# bb-meter-mk-1_0.net
KiCad netlist of a schematic drawn in EAGLE
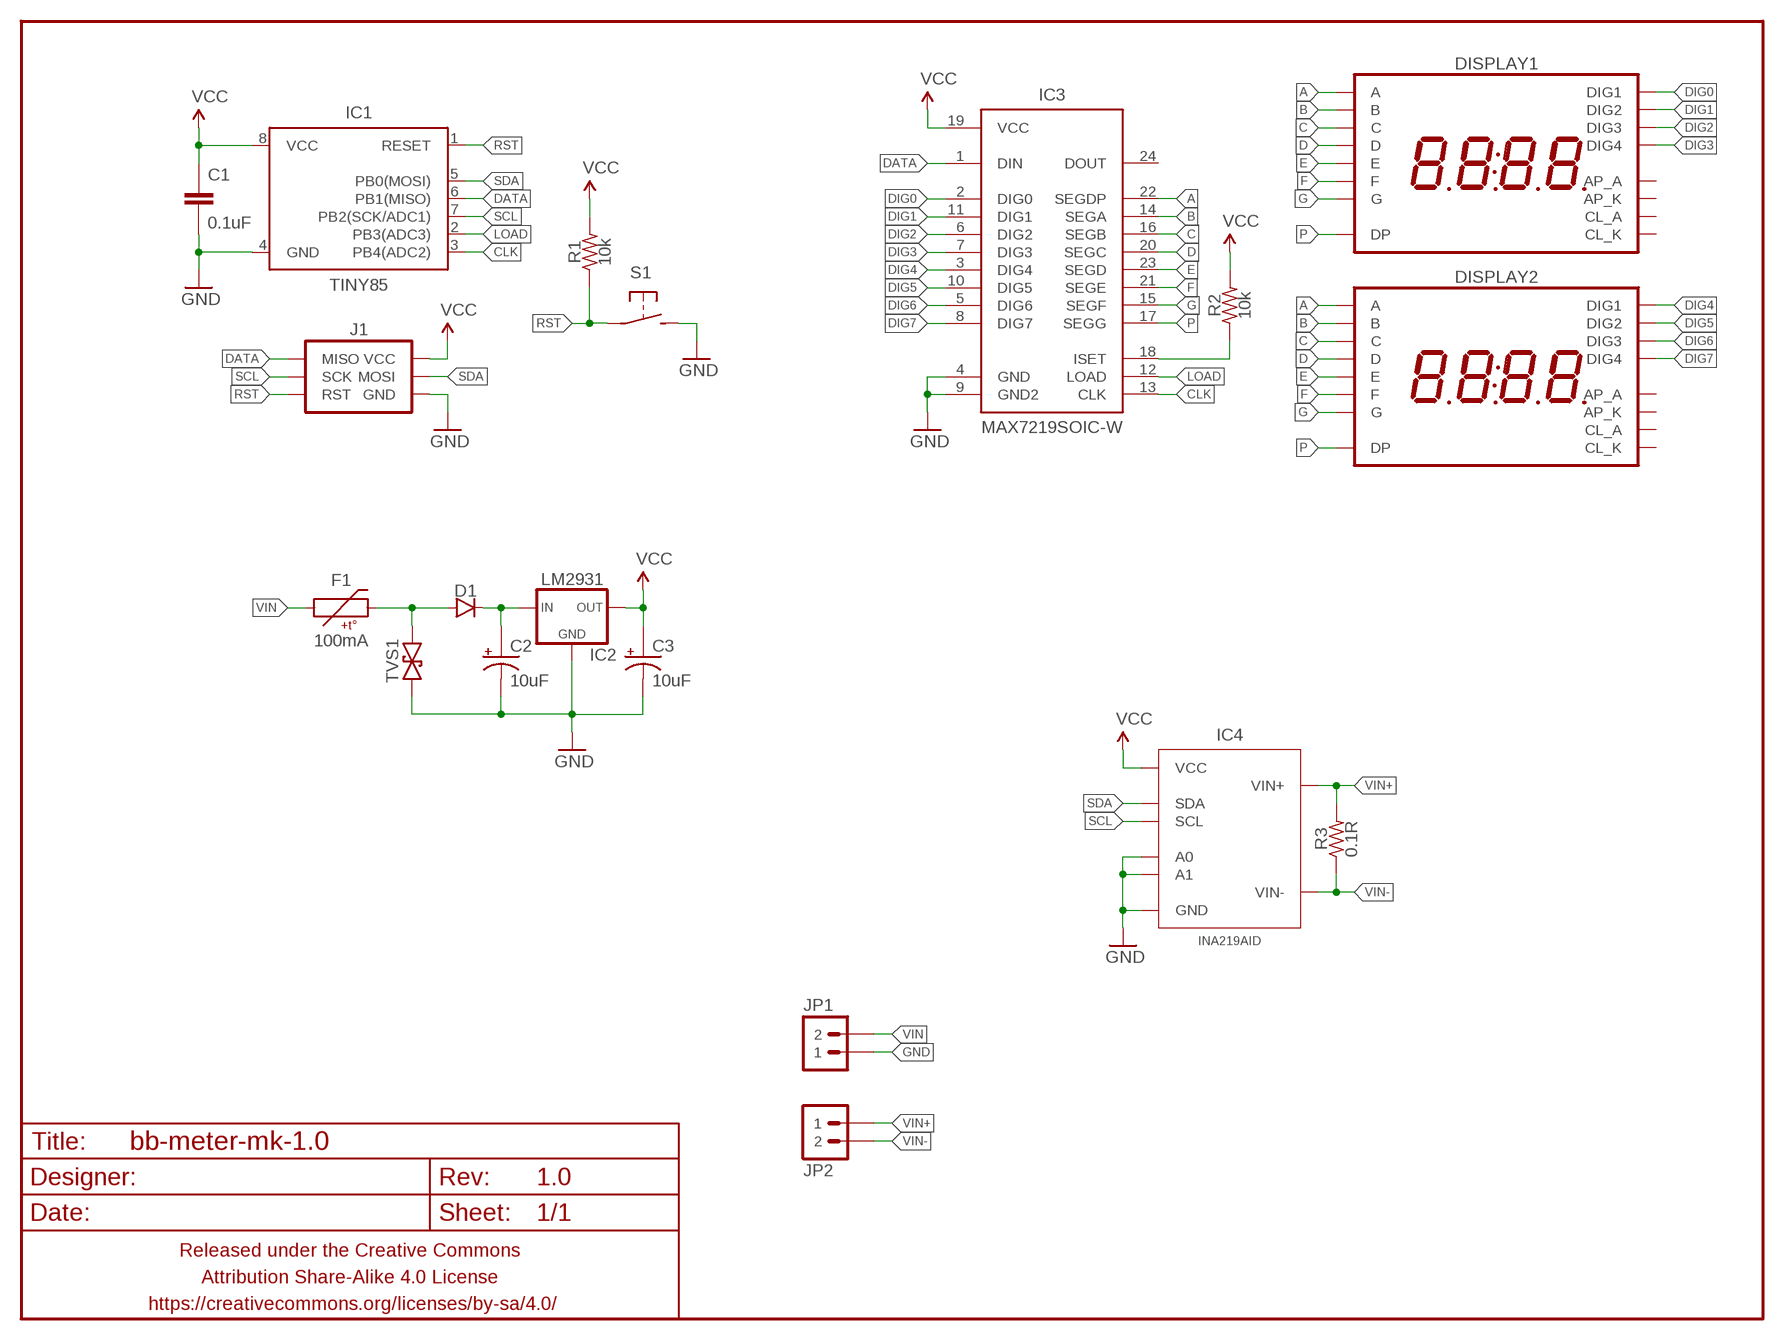
[diagram p0: schematic, sheet 1]

(export (version "E")
  (design (tool "Eeschema 10.0.6"))
  (components
    (comp (ref "C1")
      (value "0.1uF")
      (footprint "eagle-import:C025-024X044")
      (libsource (lib "eagle-import") (part "CAPACITOR-CERAMIC025-024X044"))
    )
    (comp (ref "C2")
      (value "10uF")
      (footprint "eagle-import:E2,5-5")
      (libsource (lib "eagle-import") (part "CAPACITOR-POLARIZEDE2.5-5"))
    )
    (comp (ref "C3")
      (value "10uF")
      (footprint "eagle-import:E2,5-5")
      (libsource (lib "eagle-import") (part "CAPACITOR-POLARIZEDE2.5-5"))
    )
    (comp (ref "D1")
      (value "DIODEPTH-10.68MM")
      (footprint "eagle-import:DIODE-10.16MM")
      (libsource (lib "eagle-import") (part "DIODEPTH-10.68MM"))
    )
    (comp (ref "DISPLAY1")
      (value "7SEG_4DIGIT_COLON_APOS")
      (footprint "eagle-import:7SEG_4DIG_10MM")
      (libsource (lib "eagle-import") (part "7SEG_4DIGIT_COLON_APOS"))
    )
    (comp (ref "DISPLAY2")
      (value "7SEG_4DIGIT_COLON_APOS")
      (footprint "eagle-import:7SEG_4DIG_10MM")
      (libsource (lib "eagle-import") (part "7SEG_4DIGIT_COLON_APOS"))
    )
    (comp (ref "F1")
      (value "100mA")
      (footprint "eagle-import:PTC-PTH-5.08MM")
      (libsource (lib "eagle-import") (part "PTCPTH-5.08MM"))
    )
    (comp (ref "FRAME1")
      (value "FRAME-LETTERNO_PACKAGE")
      (footprint "eagle-import:DUMMY")
      (fields (field (name "DESIGNER") "schizobovine") (field (name "VERSION") "1.0"))
      (libsource (lib "eagle-import") (part "FRAME-LETTERNO_PACKAGE"))
    )
    (comp (ref "IC1")
      (value "TINY85")
      (footprint "eagle-import:DIP08")
      (libsource (lib "eagle-import") (part "ATTINY45TINY85-20-DIP"))
    )
    (comp (ref "IC2")
      (value "LM2931")
      (footprint "eagle-import:TO-92-AMMO")
      (libsource (lib "eagle-import") (part "V_REG_78XXTO-92-INLINE"))
    )
    (comp (ref "IC3")
      (value "MAX7219SOIC-W")
      (footprint "eagle-import:SO24W")
      (libsource (lib "eagle-import") (part "MAX7219SOIC-W"))
    )
    (comp (ref "IC4")
      (value "INA219AID")
      (footprint "eagle-import:SO08")
      (libsource (lib "eagle-import") (part "INA219SOIC8"))
    )
    (comp (ref "J1")
      (value "AVR_SPI_PRG_6PTH")
      (footprint "eagle-import:2X3")
      (libsource (lib "eagle-import") (part "AVR_SPI_PRG_6PTH"))
    )
    (comp (ref "JP1")
      (value "M02PTH-CENTERED-R+")
      (footprint "eagle-import:1X02-CENTER-R+")
      (libsource (lib "eagle-import") (part "M02PTH-CENTERED-R+"))
    )
    (comp (ref "JP2")
      (value "M02PTH-CENTERED")
      (footprint "eagle-import:1X02-CENTER")
      (libsource (lib "eagle-import") (part "M02PTH-CENTERED"))
    )
    (comp (ref "R1")
      (value "10k")
      (footprint "eagle-import:RESISTOR-AXIAL-PTH-6.35MM")
      (libsource (lib "eagle-import") (part "RESISTORPTH-AXIAL-6.35MM"))
    )
    (comp (ref "R2")
      (value "10k")
      (footprint "eagle-import:R0805")
      (libsource (lib "eagle-import") (part "RESISTORR0805"))
    )
    (comp (ref "R3")
      (value "0.1R")
      (footprint "eagle-import:RESISTOR-AXIAL-PTH-10.16MM")
      (libsource (lib "eagle-import") (part "RESISTORPTH-AXIAL-10.16MM"))
    )
    (comp (ref "S1")
      (value "SPST-NO-TACT6MM-PTH-SMALL-PADS")
      (footprint "eagle-import:DTS-6-SMALL-PADS")
      (libsource (lib "eagle-import") (part "SPST-NO-TACT6MM-PTH-SMALL-PADS"))
    )
    (comp (ref "TVS1")
      (value "TVSDO-41-10.16MM")
      (footprint "eagle-import:DO-41-TVS-BI-10.16MM")
      (libsource (lib "eagle-import") (part "TVSDO-41-10.16MM"))
    )
  )
  (nets
    (net (code "1") (name "A") (class "Default")
      (node (ref "DISPLAY1") (pin "14") (pinfunction "A_14") (pintype "passive"))
      (node (ref "DISPLAY2") (pin "14") (pinfunction "A_14") (pintype "passive"))
      (node (ref "IC3") (pin "22") (pinfunction "SEGDP_22") (pintype "bidirectional"))
    )
    (net (code "2") (name "B") (class "Default")
      (node (ref "DISPLAY1") (pin "16") (pinfunction "B_16") (pintype "passive"))
      (node (ref "DISPLAY2") (pin "16") (pinfunction "B_16") (pintype "passive"))
      (node (ref "IC3") (pin "14") (pinfunction "SEGA_14") (pintype "bidirectional"))
    )
    (net (code "3") (name "C") (class "Default")
      (node (ref "DISPLAY1") (pin "13") (pinfunction "C_13") (pintype "passive"))
      (node (ref "DISPLAY2") (pin "13") (pinfunction "C_13") (pintype "passive"))
      (node (ref "IC3") (pin "16") (pinfunction "SEGB_16") (pintype "bidirectional"))
    )
    (net (code "4") (name "CLK") (class "Default")
      (node (ref "IC1") (pin "3") (pinfunction "PB4(ADC2)_3") (pintype "bidirectional"))
      (node (ref "IC3") (pin "13") (pinfunction "CLK_13") (pintype "bidirectional"))
    )
    (net (code "5") (name "D") (class "Default")
      (node (ref "DISPLAY1") (pin "3") (pinfunction "D_3") (pintype "passive"))
      (node (ref "DISPLAY2") (pin "3") (pinfunction "D_3") (pintype "passive"))
      (node (ref "IC3") (pin "20") (pinfunction "SEGC_20") (pintype "bidirectional"))
    )
    (net (code "6") (name "DATA") (class "Default")
      (node (ref "IC1") (pin "6") (pinfunction "PB1(MISO)_6") (pintype "bidirectional"))
      (node (ref "IC3") (pin "1") (pinfunction "DIN_1") (pintype "bidirectional"))
      (node (ref "J1") (pin "1") (pinfunction "MISO_1") (pintype "passive"))
    )
    (net (code "7") (name "DIG0") (class "Default")
      (node (ref "DISPLAY1") (pin "1") (pinfunction "DIG1_1") (pintype "passive"))
      (node (ref "IC3") (pin "2") (pinfunction "DIG0_2") (pintype "bidirectional"))
    )
    (net (code "8") (name "DIG1") (class "Default")
      (node (ref "DISPLAY1") (pin "2") (pinfunction "DIG2_2") (pintype "passive"))
      (node (ref "IC3") (pin "11") (pinfunction "DIG1_11") (pintype "bidirectional"))
    )
    (net (code "9") (name "DIG2") (class "Default")
      (node (ref "DISPLAY1") (pin "6") (pinfunction "DIG3_6") (pintype "passive"))
      (node (ref "IC3") (pin "6") (pinfunction "DIG2_6") (pintype "bidirectional"))
    )
    (net (code "10") (name "DIG3") (class "Default")
      (node (ref "DISPLAY1") (pin "8") (pinfunction "DIG4_8") (pintype "passive"))
      (node (ref "IC3") (pin "7") (pinfunction "DIG3_7") (pintype "bidirectional"))
    )
    (net (code "11") (name "DIG4") (class "Default")
      (node (ref "DISPLAY2") (pin "1") (pinfunction "DIG1_1") (pintype "passive"))
      (node (ref "IC3") (pin "3") (pinfunction "DIG4_3") (pintype "bidirectional"))
    )
    (net (code "12") (name "DIG5") (class "Default")
      (node (ref "DISPLAY2") (pin "2") (pinfunction "DIG2_2") (pintype "passive"))
      (node (ref "IC3") (pin "10") (pinfunction "DIG5_10") (pintype "bidirectional"))
    )
    (net (code "13") (name "DIG6") (class "Default")
      (node (ref "DISPLAY2") (pin "6") (pinfunction "DIG3_6") (pintype "passive"))
      (node (ref "IC3") (pin "5") (pinfunction "DIG6_5") (pintype "bidirectional"))
    )
    (net (code "14") (name "DIG7") (class "Default")
      (node (ref "DISPLAY2") (pin "8") (pinfunction "DIG4_8") (pintype "passive"))
      (node (ref "IC3") (pin "8") (pinfunction "DIG7_8") (pintype "bidirectional"))
    )
    (net (code "15") (name "E") (class "Default")
      (node (ref "DISPLAY1") (pin "5") (pinfunction "E_5") (pintype "passive"))
      (node (ref "DISPLAY2") (pin "5") (pinfunction "E_5") (pintype "passive"))
      (node (ref "IC3") (pin "23") (pinfunction "SEGD_23") (pintype "bidirectional"))
    )
    (net (code "16") (name "F") (class "Default")
      (node (ref "DISPLAY1") (pin "11") (pinfunction "F_11") (pintype "passive"))
      (node (ref "DISPLAY2") (pin "11") (pinfunction "F_11") (pintype "passive"))
      (node (ref "IC3") (pin "21") (pinfunction "SEGE_21") (pintype "bidirectional"))
    )
    (net (code "17") (name "G") (class "Default")
      (node (ref "DISPLAY1") (pin "15") (pinfunction "G_15") (pintype "passive"))
      (node (ref "DISPLAY2") (pin "15") (pinfunction "G_15") (pintype "passive"))
      (node (ref "IC3") (pin "15") (pinfunction "SEGF_15") (pintype "bidirectional"))
    )
    (net (code "18") (name "GND") (class "Default")
      (node (ref "C1") (pin "2") (pinfunction "2_2") (pintype "passive"))
      (node (ref "C2") (pin "-") (pinfunction "-_-") (pintype "passive"))
      (node (ref "C3") (pin "-") (pinfunction "-_-") (pintype "passive"))
      (node (ref "IC1") (pin "4") (pinfunction "GND_4") (pintype "bidirectional"))
      (node (ref "IC2") (pin "2") (pinfunction "GND_2") (pintype "bidirectional"))
      (node (ref "IC3") (pin "4") (pinfunction "GND_4") (pintype "bidirectional"))
      (node (ref "IC3") (pin "9") (pinfunction "GND2_9") (pintype "bidirectional"))
      (node (ref "IC4") (pin "1") (pinfunction "A1_1") (pintype "bidirectional"))
      (node (ref "IC4") (pin "2") (pinfunction "A0_2") (pintype "bidirectional"))
      (node (ref "IC4") (pin "6") (pinfunction "GND_6") (pintype "bidirectional"))
      (node (ref "J1") (pin "6") (pinfunction "GND_6") (pintype "passive"))
      (node (ref "JP1") (pin "1") (pinfunction "1_1") (pintype "passive"))
      (node (ref "S1") (pin "3") (pinfunction "2_3") (pintype "passive"))
      (node (ref "S1") (pin "4") (pinfunction "2_4") (pintype "passive"))
      (node (ref "TVS1") (pin "P$1") (pinfunction "1_P$1") (pintype "passive"))
    )
    (net (code "19") (name "LOAD") (class "Default")
      (node (ref "IC1") (pin "2") (pinfunction "PB3(ADC3)_2") (pintype "bidirectional"))
      (node (ref "IC3") (pin "12") (pinfunction "LOAD_12") (pintype "bidirectional"))
    )
    (net (code "20") (name "Net-(F1-2)") (class "Default")
      (node (ref "D1") (pin "A") (pinfunction "A_A") (pintype "passive"))
      (node (ref "F1") (pin "P$2") (pinfunction "2_P$2") (pintype "passive"))
      (node (ref "TVS1") (pin "P$2") (pinfunction "2_P$2") (pintype "passive"))
    )
    (net (code "21") (name "Net-(IC2-IN)") (class "Default")
      (node (ref "C2") (pin "+") (pinfunction "+_+") (pintype "passive"))
      (node (ref "D1") (pin "C") (pinfunction "C_C") (pintype "passive"))
      (node (ref "IC2") (pin "1") (pinfunction "IN_1") (pintype "bidirectional"))
    )
    (net (code "22") (name "Net-(IC3-ISET)") (class "Default")
      (node (ref "IC3") (pin "18") (pinfunction "ISET_18") (pintype "bidirectional"))
      (node (ref "R2") (pin "1") (pinfunction "1_1") (pintype "passive"))
    )
    (net (code "23") (name "P") (class "Default")
      (node (ref "DISPLAY1") (pin "7") (pinfunction "DP_7") (pintype "passive"))
      (node (ref "DISPLAY2") (pin "7") (pinfunction "DP_7") (pintype "passive"))
      (node (ref "IC3") (pin "17") (pinfunction "SEGG_17") (pintype "bidirectional"))
    )
    (net (code "24") (name "RST") (class "Default")
      (node (ref "IC1") (pin "1") (pinfunction "RESET_1") (pintype "bidirectional"))
      (node (ref "J1") (pin "5") (pinfunction "RST_5") (pintype "passive"))
      (node (ref "R1") (pin "P$1") (pinfunction "1_P$1") (pintype "passive"))
      (node (ref "S1") (pin "1") (pinfunction "1_1") (pintype "passive"))
      (node (ref "S1") (pin "2") (pinfunction "1_2") (pintype "passive"))
    )
    (net (code "25") (name "SCL") (class "Default")
      (node (ref "IC1") (pin "7") (pinfunction "PB2(SCK/ADC1)_7") (pintype "bidirectional"))
      (node (ref "IC4") (pin "4") (pinfunction "SCL_4") (pintype "bidirectional"))
      (node (ref "J1") (pin "3") (pinfunction "SCK_3") (pintype "passive"))
    )
    (net (code "26") (name "SDA") (class "Default")
      (node (ref "IC1") (pin "5") (pinfunction "PB0(MOSI)_5") (pintype "bidirectional"))
      (node (ref "IC4") (pin "3") (pinfunction "SDA_3") (pintype "bidirectional"))
      (node (ref "J1") (pin "4") (pinfunction "MOSI_4") (pintype "passive"))
    )
    (net (code "27") (name "VCC") (class "Default")
      (node (ref "C1") (pin "1") (pinfunction "1_1") (pintype "passive"))
      (node (ref "C3") (pin "+") (pinfunction "+_+") (pintype "passive"))
      (node (ref "IC1") (pin "8") (pinfunction "VCC_8") (pintype "bidirectional"))
      (node (ref "IC2") (pin "3") (pinfunction "OUT_3") (pintype "bidirectional"))
      (node (ref "IC3") (pin "19") (pinfunction "VCC_19") (pintype "bidirectional"))
      (node (ref "IC4") (pin "5") (pinfunction "VCC_5") (pintype "bidirectional"))
      (node (ref "J1") (pin "2") (pinfunction "VCC_2") (pintype "passive"))
      (node (ref "R1") (pin "P$2") (pinfunction "2_P$2") (pintype "passive"))
      (node (ref "R2") (pin "2") (pinfunction "2_2") (pintype "passive"))
    )
    (net (code "28") (name "VIN") (class "Default")
      (node (ref "F1") (pin "P$1") (pinfunction "1_P$1") (pintype "passive"))
      (node (ref "JP1") (pin "2") (pinfunction "2_2") (pintype "passive"))
    )
    (net (code "29") (name "VIN+") (class "Default")
      (node (ref "IC4") (pin "8") (pinfunction "VIN+_8") (pintype "bidirectional"))
      (node (ref "JP2") (pin "1") (pinfunction "1_1") (pintype "passive"))
      (node (ref "R3") (pin "P$2") (pinfunction "2_P$2") (pintype "passive"))
    )
    (net (code "30") (name "VIN-") (class "Default")
      (node (ref "IC4") (pin "7") (pinfunction "VIN-_7") (pintype "bidirectional"))
      (node (ref "JP2") (pin "2") (pinfunction "2_2") (pintype "passive"))
      (node (ref "R3") (pin "P$1") (pinfunction "1_P$1") (pintype "passive"))
    )
    (net (code "31") (name "unconnected-(DISPLAY1-AP_A-Pad10)") (class "Default")
      (node (ref "DISPLAY1") (pin "10") (pinfunction "AP_A_10") (pintype "bidirectional"))
    )
    (net (code "32") (name "unconnected-(DISPLAY1-AP_K-Pad9)") (class "Default")
      (node (ref "DISPLAY1") (pin "9") (pinfunction "AP_K_9") (pintype "bidirectional"))
    )
    (net (code "33") (name "unconnected-(DISPLAY1-CL_A-Pad4)") (class "Default")
      (node (ref "DISPLAY1") (pin "4") (pinfunction "CL_A_4") (pintype "passive"))
    )
    (net (code "34") (name "unconnected-(DISPLAY1-CL_K-Pad12)") (class "Default")
      (node (ref "DISPLAY1") (pin "12") (pinfunction "CL_K_12") (pintype "passive"))
    )
    (net (code "35") (name "unconnected-(DISPLAY2-AP_A-Pad10)") (class "Default")
      (node (ref "DISPLAY2") (pin "10") (pinfunction "AP_A_10") (pintype "bidirectional"))
    )
    (net (code "36") (name "unconnected-(DISPLAY2-AP_K-Pad9)") (class "Default")
      (node (ref "DISPLAY2") (pin "9") (pinfunction "AP_K_9") (pintype "bidirectional"))
    )
    (net (code "37") (name "unconnected-(DISPLAY2-CL_A-Pad4)") (class "Default")
      (node (ref "DISPLAY2") (pin "4") (pinfunction "CL_A_4") (pintype "passive"))
    )
    (net (code "38") (name "unconnected-(DISPLAY2-CL_K-Pad12)") (class "Default")
      (node (ref "DISPLAY2") (pin "12") (pinfunction "CL_K_12") (pintype "passive"))
    )
    (net (code "39") (name "unconnected-(IC3-DOUT-Pad24)") (class "Default")
      (node (ref "IC3") (pin "24") (pinfunction "DOUT_24") (pintype "bidirectional"))
    )
  )
)
